# 2S_BATTERY_PROTECTION_SCH.net
KiCad netlist of a schematic drawn in Altium Designer
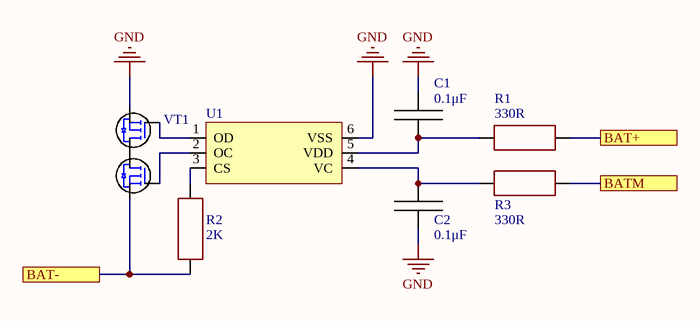
[diagram p0: 2S_BATTERY_PROTECTION_SCH.SchDoc]

(export (version "E")
  (design (tool "Eeschema 10.0.6"))
  (components
    (comp (ref "C1")
      (value "0.1μF")
      (footprint "CAP: 0402")
      (fields (field (name "VOLTAGE") "??V") (field (name "Comment") "Cap_0402"))
      (libsource (lib "capacitor") (part "Cap_0402"))
    )
    (comp (ref "C2")
      (value "0.1μF")
      (footprint "CAP: 0402")
      (fields (field (name "VOLTAGE") "??V") (field (name "Comment") "Cap_0402"))
      (libsource (lib "capacitor") (part "Cap_0402"))
    )
    (comp (ref "R1")
      (value "330R")
      (footprint "standard-case:RES: 0402")
      (fields (field (name "TOLERANCE") "±5%"))
      (libsource (lib "resistor") (part "Resistor_0402"))
    )
    (comp (ref "R2")
      (value "2K")
      (footprint "standard-case:RES: 0402")
      (fields (field (name "TOLERANCE") "±5%"))
      (libsource (lib "") (part "Resistor_0402_1"))
    )
    (comp (ref "R3")
      (value "330R")
      (footprint "standard-case:RES: 0402")
      (fields (field (name "TOLERANCE") "±5%"))
      (libsource (lib "resistor") (part "Resistor_0402"))
    )
    (comp (ref "U1")
      (value "HY2120")
      (footprint "SOT-23-6")
      (description "2-cell lithium-ion/lithium polymer rechargeable battery\r\nprotection")
      (fields (field (name "MANUFACTURER") "HYCON"))
      (libsource (lib "MY_INT_LIB") (part "HY2120"))
    )
    (comp (ref "VT1")
      (value "8205A")
      (footprint "SOT-23-6")
      (description "MOSFET N-CHANNEL 20V 5A")
      (fields (field (name "MANUFACTURER") "UMW"))
      (libsource (lib "MY_INT_LIB") (part "8205A"))
    )
  )
  (nets
    (net (code "1") (name "/BAT+") (class "Default")
      (node (ref "R1") (pin "2") (pinfunction "2_2") (pintype "passive"))
    )
    (net (code "2") (name "/BAT-") (class "Default")
      (node (ref "R2") (pin "1") (pinfunction "1_1") (pintype "passive"))
      (node (ref "VT1") (pin "3") (pintype "power_in"))
    )
    (net (code "3") (name "/BATM") (class "Default")
      (node (ref "R3") (pin "2") (pinfunction "2_2") (pintype "passive"))
    )
    (net (code "4") (name "GND") (class "Default")
      (node (ref "C1") (pin "2") (pinfunction "2_2") (pintype "passive"))
      (node (ref "C2") (pin "1") (pinfunction "1_1") (pintype "passive"))
      (node (ref "U1") (pin "6") (pinfunction "VSS_6") (pintype "passive"))
      (node (ref "VT1") (pin "1") (pintype "power_in"))
    )
    (net (code "5") (name "Net-(U1-CS)") (class "Default")
      (node (ref "R2") (pin "2") (pinfunction "2_2") (pintype "passive"))
      (node (ref "U1") (pin "3") (pinfunction "CS_3") (pintype "passive"))
    )
    (net (code "6") (name "Net-(U1-OC)") (class "Default")
      (node (ref "U1") (pin "2") (pinfunction "OC_2") (pintype "passive"))
      (node (ref "VT1") (pin "4") (pintype "power_in"))
    )
    (net (code "7") (name "Net-(U1-OD)") (class "Default")
      (node (ref "U1") (pin "1") (pinfunction "OD_1") (pintype "passive"))
      (node (ref "VT1") (pin "6") (pintype "power_in"))
    )
    (net (code "8") (name "Net-(U1-VC)") (class "Default")
      (node (ref "C2") (pin "2") (pinfunction "2_2") (pintype "passive"))
      (node (ref "R3") (pin "1") (pinfunction "1_1") (pintype "passive"))
      (node (ref "U1") (pin "4") (pinfunction "VC_4") (pintype "passive"))
    )
    (net (code "9") (name "Net-(U1-VDD)") (class "Default")
      (node (ref "C1") (pin "1") (pinfunction "1_1") (pintype "passive"))
      (node (ref "R1") (pin "1") (pinfunction "1_1") (pintype "passive"))
      (node (ref "U1") (pin "5") (pinfunction "VDD_5") (pintype "passive"))
    )
    (net (code "10") (name "Net-(VT1-Pad2)") (class "Default")
      (node (ref "VT1") (pin "2") (pintype "power_in"))
      (node (ref "VT1") (pin "5") (pintype "power_in"))
    )
  )
)
